# ControleLeds.net
KiCad netlist of a schematic drawn in Altium Designer
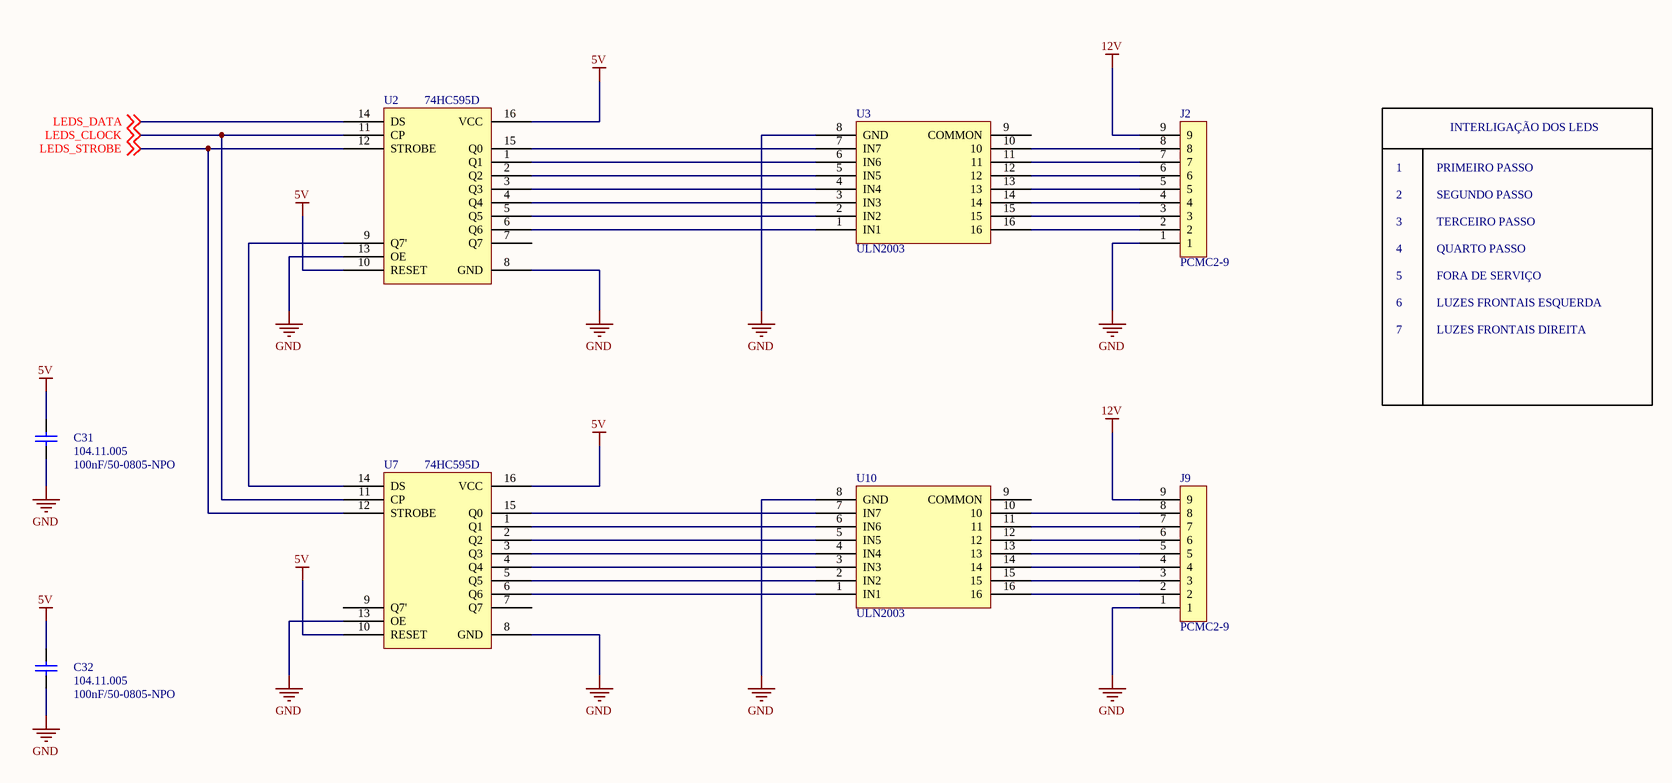
[diagram p0: ControleLeds.SchDoc]

(export (version "E")
  (design (tool "Eeschema 10.0.6"))
  (components
    (comp (ref "C31")
      (value "100nF/50-0805-NPO")
      (footprint "0805-REVISADO ONDA")
      (fields (field (name "ERP") "104.11.005"))
      (libsource (lib "AquinoLib") (part "100nF/50-0805-NPO"))
    )
    (comp (ref "C32")
      (value "100nF/50-0805-NPO")
      (footprint "0805-REVISADO ONDA")
      (fields (field (name "ERP") "104.11.005"))
      (libsource (lib "AquinoLib") (part "100nF/50-0805-NPO"))
    )
    (comp (ref "J2") (value "PCMC2-9") (footprint "PCMC2-9") (libsource (lib "AquinoLib") (part "PCMC2-9")))
    (comp (ref "J9") (value "PCMC2-9") (footprint "PCMC2-9") (libsource (lib "AquinoLib") (part "PCMC2-9")))
    (comp (ref "U2")
      (value "74HC595D")
      (footprint "SOIC 16 PINOS")
      (libsource (lib "ChaveDigital3") (part "74HC595D"))
    )
    (comp (ref "U3")
      (value "ULN2003")
      (footprint "SOIC 16 PINOS")
      (libsource (lib "AquinoLib") (part "ULN2003"))
    )
    (comp (ref "U7")
      (value "74HC595D")
      (footprint "SOIC 16 PINOS")
      (libsource (lib "ChaveDigital3") (part "74HC595D"))
    )
    (comp (ref "U10")
      (value "ULN2003")
      (footprint "SOIC 16 PINOS")
      (libsource (lib "AquinoLib") (part "ULN2003"))
    )
  )
  (nets
    (net (code "1") (name "5V") (class "Default")
      (node (ref "C31") (pin "2") (pinfunction "2_2") (pintype "passive"))
      (node (ref "C32") (pin "2") (pinfunction "2_2") (pintype "passive"))
      (node (ref "U2") (pin "10") (pinfunction "RESET_10") (pintype "passive"))
      (node (ref "U2") (pin "16") (pinfunction "VCC_16") (pintype "passive"))
      (node (ref "U7") (pin "10") (pinfunction "RESET_10") (pintype "passive"))
      (node (ref "U7") (pin "16") (pinfunction "VCC_16") (pintype "passive"))
    )
    (net (code "2") (name "12V") (class "Default")
      (node (ref "J2") (pin "9") (pinfunction "9_9") (pintype "passive"))
      (node (ref "J9") (pin "9") (pinfunction "9_9") (pintype "passive"))
    )
    (net (code "3") (name "GND") (class "Default")
      (node (ref "C31") (pin "1") (pinfunction "1_1") (pintype "passive"))
      (node (ref "C32") (pin "1") (pinfunction "1_1") (pintype "passive"))
      (node (ref "J2") (pin "1") (pinfunction "1_1") (pintype "passive"))
      (node (ref "J9") (pin "1") (pinfunction "1_1") (pintype "passive"))
      (node (ref "U10") (pin "8") (pinfunction "GND_8") (pintype "passive"))
      (node (ref "U2") (pin "13") (pinfunction "OE_13") (pintype "passive"))
      (node (ref "U2") (pin "8") (pinfunction "GND_8") (pintype "passive"))
      (node (ref "U3") (pin "8") (pinfunction "GND_8") (pintype "passive"))
      (node (ref "U7") (pin "13") (pinfunction "OE_13") (pintype "passive"))
      (node (ref "U7") (pin "8") (pinfunction "GND_8") (pintype "passive"))
    )
    (net (code "4") (name "LEDS_CLOCK") (class "Default")
      (node (ref "U2") (pin "11") (pinfunction "CP_11") (pintype "passive"))
      (node (ref "U7") (pin "11") (pinfunction "CP_11") (pintype "passive"))
    )
    (net (code "5") (name "LEDS_DATA") (class "Default")
      (node (ref "U2") (pin "14") (pinfunction "DS_14") (pintype "passive"))
    )
    (net (code "6") (name "LEDS_STROBE") (class "Default")
      (node (ref "U2") (pin "12") (pinfunction "STROBE_12") (pintype "passive"))
      (node (ref "U7") (pin "12") (pinfunction "STROBE_12") (pintype "passive"))
    )
    (net (code "7") (name "Net-(J2-Pad2)") (class "Default")
      (node (ref "J2") (pin "2") (pinfunction "2_2") (pintype "passive"))
      (node (ref "U3") (pin "16") (pinfunction "16_16") (pintype "passive"))
    )
    (net (code "8") (name "Net-(J2-Pad3)") (class "Default")
      (node (ref "J2") (pin "3") (pinfunction "3_3") (pintype "passive"))
      (node (ref "U3") (pin "15") (pinfunction "15_15") (pintype "passive"))
    )
    (net (code "9") (name "Net-(J2-Pad4)") (class "Default")
      (node (ref "J2") (pin "4") (pinfunction "4_4") (pintype "passive"))
      (node (ref "U3") (pin "14") (pinfunction "14_14") (pintype "passive"))
    )
    (net (code "10") (name "Net-(J2-Pad5)") (class "Default")
      (node (ref "J2") (pin "5") (pinfunction "5_5") (pintype "passive"))
      (node (ref "U3") (pin "13") (pinfunction "13_13") (pintype "passive"))
    )
    (net (code "11") (name "Net-(J2-Pad6)") (class "Default")
      (node (ref "J2") (pin "6") (pinfunction "6_6") (pintype "passive"))
      (node (ref "U3") (pin "12") (pinfunction "12_12") (pintype "passive"))
    )
    (net (code "12") (name "Net-(J2-Pad7)") (class "Default")
      (node (ref "J2") (pin "7") (pinfunction "7_7") (pintype "passive"))
      (node (ref "U3") (pin "11") (pinfunction "11_11") (pintype "passive"))
    )
    (net (code "13") (name "Net-(J2-Pad8)") (class "Default")
      (node (ref "J2") (pin "8") (pinfunction "8_8") (pintype "passive"))
      (node (ref "U3") (pin "10") (pinfunction "10_10") (pintype "passive"))
    )
    (net (code "14") (name "Net-(J9-Pad2)") (class "Default")
      (node (ref "J9") (pin "2") (pinfunction "2_2") (pintype "passive"))
      (node (ref "U10") (pin "16") (pinfunction "16_16") (pintype "passive"))
    )
    (net (code "15") (name "Net-(J9-Pad3)") (class "Default")
      (node (ref "J9") (pin "3") (pinfunction "3_3") (pintype "passive"))
      (node (ref "U10") (pin "15") (pinfunction "15_15") (pintype "passive"))
    )
    (net (code "16") (name "Net-(J9-Pad4)") (class "Default")
      (node (ref "J9") (pin "4") (pinfunction "4_4") (pintype "passive"))
      (node (ref "U10") (pin "14") (pinfunction "14_14") (pintype "passive"))
    )
    (net (code "17") (name "Net-(J9-Pad5)") (class "Default")
      (node (ref "J9") (pin "5") (pinfunction "5_5") (pintype "passive"))
      (node (ref "U10") (pin "13") (pinfunction "13_13") (pintype "passive"))
    )
    (net (code "18") (name "Net-(J9-Pad6)") (class "Default")
      (node (ref "J9") (pin "6") (pinfunction "6_6") (pintype "passive"))
      (node (ref "U10") (pin "12") (pinfunction "12_12") (pintype "passive"))
    )
    (net (code "19") (name "Net-(J9-Pad7)") (class "Default")
      (node (ref "J9") (pin "7") (pinfunction "7_7") (pintype "passive"))
      (node (ref "U10") (pin "11") (pinfunction "11_11") (pintype "passive"))
    )
    (net (code "20") (name "Net-(J9-Pad8)") (class "Default")
      (node (ref "J9") (pin "8") (pinfunction "8_8") (pintype "passive"))
      (node (ref "U10") (pin "10") (pinfunction "10_10") (pintype "passive"))
    )
    (net (code "21") (name "Net-(U2-Q0)") (class "Default")
      (node (ref "U2") (pin "15") (pinfunction "Q0_15") (pintype "passive"))
      (node (ref "U3") (pin "7") (pinfunction "IN7_7") (pintype "passive"))
    )
    (net (code "22") (name "Net-(U2-Q1)") (class "Default")
      (node (ref "U2") (pin "1") (pinfunction "Q1_1") (pintype "passive"))
      (node (ref "U3") (pin "6") (pinfunction "IN6_6") (pintype "passive"))
    )
    (net (code "23") (name "Net-(U2-Q2)") (class "Default")
      (node (ref "U2") (pin "2") (pinfunction "Q2_2") (pintype "passive"))
      (node (ref "U3") (pin "5") (pinfunction "IN5_5") (pintype "passive"))
    )
    (net (code "24") (name "Net-(U2-Q3)") (class "Default")
      (node (ref "U2") (pin "3") (pinfunction "Q3_3") (pintype "passive"))
      (node (ref "U3") (pin "4") (pinfunction "IN4_4") (pintype "passive"))
    )
    (net (code "25") (name "Net-(U2-Q4)") (class "Default")
      (node (ref "U2") (pin "4") (pinfunction "Q4_4") (pintype "passive"))
      (node (ref "U3") (pin "3") (pinfunction "IN3_3") (pintype "passive"))
    )
    (net (code "26") (name "Net-(U2-Q5)") (class "Default")
      (node (ref "U2") (pin "5") (pinfunction "Q5_5") (pintype "passive"))
      (node (ref "U3") (pin "2") (pinfunction "IN2_2") (pintype "passive"))
    )
    (net (code "27") (name "Net-(U2-Q6)") (class "Default")
      (node (ref "U2") (pin "6") (pinfunction "Q6_6") (pintype "passive"))
      (node (ref "U3") (pin "1") (pinfunction "IN1_1") (pintype "passive"))
    )
    (net (code "28") (name "Net-(U2-Q7')") (class "Default")
      (node (ref "U2") (pin "9") (pinfunction "Q7'_9") (pintype "passive"))
      (node (ref "U7") (pin "14") (pinfunction "DS_14") (pintype "passive"))
    )
    (net (code "29") (name "Net-(U10-IN1)") (class "Default")
      (node (ref "U10") (pin "1") (pinfunction "IN1_1") (pintype "passive"))
      (node (ref "U7") (pin "6") (pinfunction "Q6_6") (pintype "passive"))
    )
    (net (code "30") (name "Net-(U10-IN2)") (class "Default")
      (node (ref "U10") (pin "2") (pinfunction "IN2_2") (pintype "passive"))
      (node (ref "U7") (pin "5") (pinfunction "Q5_5") (pintype "passive"))
    )
    (net (code "31") (name "Net-(U10-IN3)") (class "Default")
      (node (ref "U10") (pin "3") (pinfunction "IN3_3") (pintype "passive"))
      (node (ref "U7") (pin "4") (pinfunction "Q4_4") (pintype "passive"))
    )
    (net (code "32") (name "Net-(U10-IN4)") (class "Default")
      (node (ref "U10") (pin "4") (pinfunction "IN4_4") (pintype "passive"))
      (node (ref "U7") (pin "3") (pinfunction "Q3_3") (pintype "passive"))
    )
    (net (code "33") (name "Net-(U10-IN5)") (class "Default")
      (node (ref "U10") (pin "5") (pinfunction "IN5_5") (pintype "passive"))
      (node (ref "U7") (pin "2") (pinfunction "Q2_2") (pintype "passive"))
    )
    (net (code "34") (name "Net-(U10-IN6)") (class "Default")
      (node (ref "U10") (pin "6") (pinfunction "IN6_6") (pintype "passive"))
      (node (ref "U7") (pin "1") (pinfunction "Q1_1") (pintype "passive"))
    )
    (net (code "35") (name "Net-(U10-IN7)") (class "Default")
      (node (ref "U10") (pin "7") (pinfunction "IN7_7") (pintype "passive"))
      (node (ref "U7") (pin "15") (pinfunction "Q0_15") (pintype "passive"))
    )
    (net (code "36") (name "unconnected-(U2-Q7-Pad7)") (class "Default")
      (node (ref "U2") (pin "7") (pinfunction "Q7_7") (pintype "passive"))
    )
    (net (code "37") (name "unconnected-(U3-COMMON-Pad9)") (class "Default")
      (node (ref "U3") (pin "9") (pinfunction "COMMON_9") (pintype "passive"))
    )
    (net (code "38") (name "unconnected-(U7-Q7'-Pad9)") (class "Default")
      (node (ref "U7") (pin "9") (pinfunction "Q7'_9") (pintype "passive"))
    )
    (net (code "39") (name "unconnected-(U7-Q7-Pad7)") (class "Default")
      (node (ref "U7") (pin "7") (pinfunction "Q7_7") (pintype "passive"))
    )
    (net (code "40") (name "unconnected-(U10-COMMON-Pad9)") (class "Default")
      (node (ref "U10") (pin "9") (pinfunction "COMMON_9") (pintype "passive"))
    )
  )
)
